# 2_MCU.net
KiCad netlist of a schematic drawn in Altium Designer
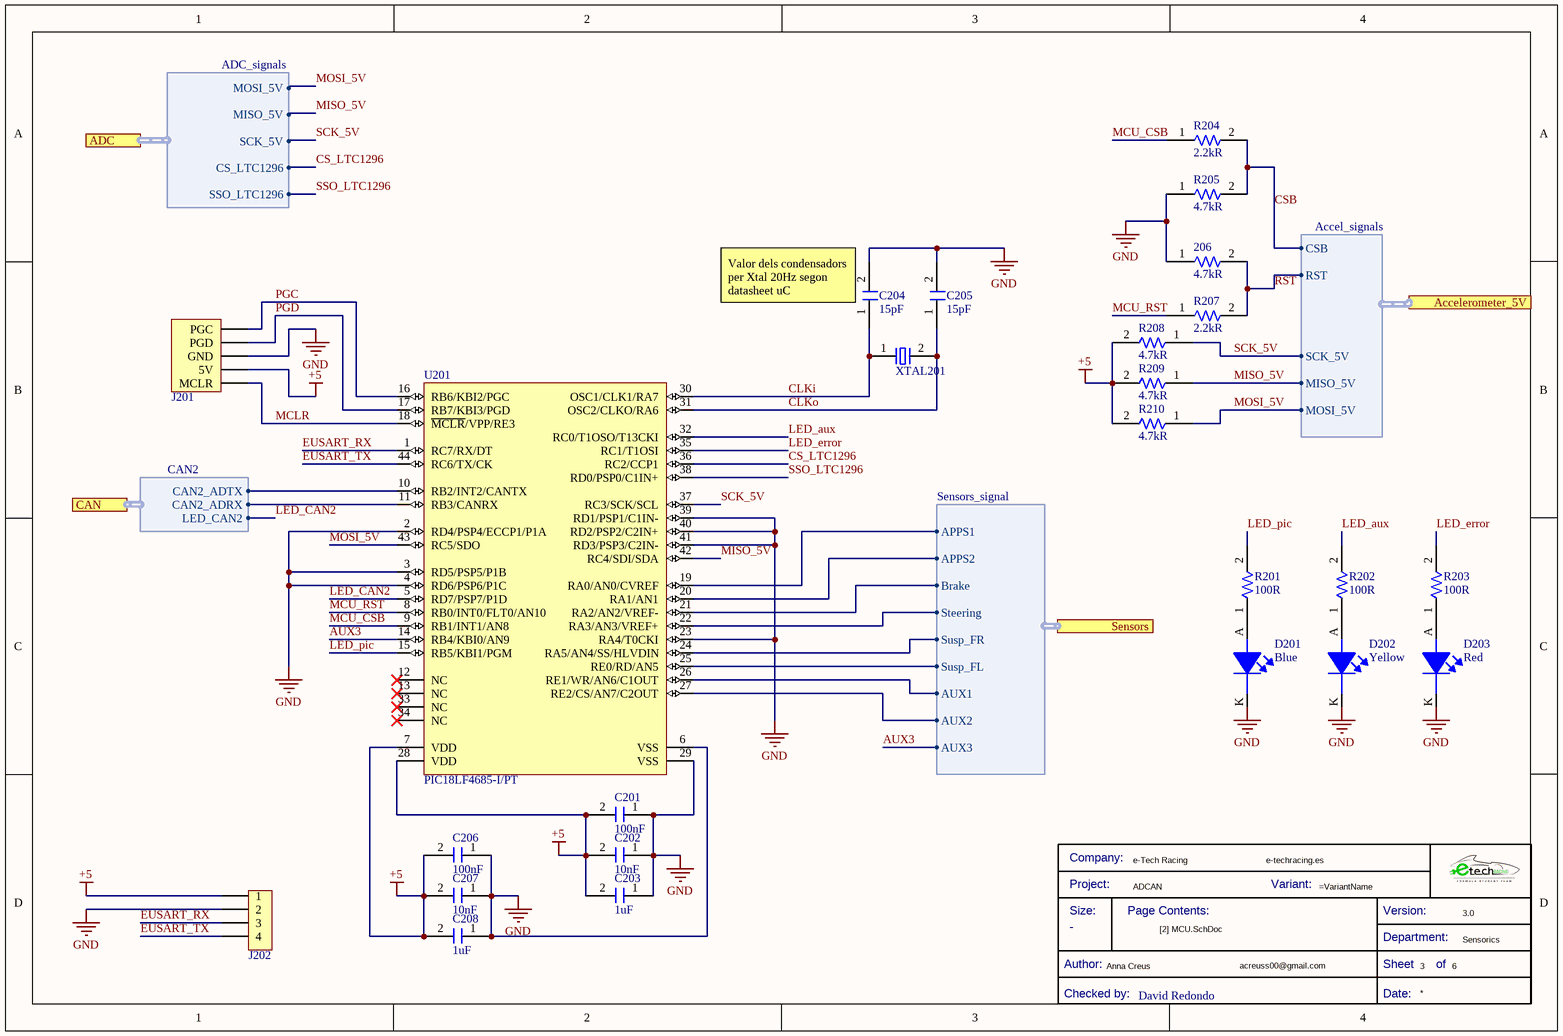
[diagram p0: [2] MCU.SchDoc]

(export (version "E")
  (design (tool "Eeschema 10.0.6"))
  (components
    (comp (ref "206")
      (value "CRS1206-FX-4701ELF")
      (footprint "R1206FTK-W")
      (description "Res Thick Film 1206 4.7K Ohm 1% 1/2W ±100ppm/°C Molded SMD T/R")
      (fields (field (name "TOLERANCE") "1%") (field (name "RESISTANCE") "4.7kR"))
      (libsource (lib "Passives") (part "R4.7K-1206FTK"))
    )
    (comp (ref "C201")
      (value "885012208009")
      (footprint "C1206FNPC-RW")
      (description "Cap, 0.1ΜF, 10V, 10%, X7R, 1206")
      (fields (field (name "TOLERANCE") "10%") (field (name "CAPACITANCE") "100nF"))
      (libsource (lib "Passives") (part "C100n-10V-1206FNPC-X7R"))
    )
    (comp (ref "C202")
      (value "885012208009")
      (footprint "C1206FNPC-RW")
      (description "Cap, 0.1ΜF, 10V, 10%, X7R, 1206")
      (fields (field (name "TOLERANCE") "10%") (field (name "CAPACITANCE") "10nF"))
      (libsource (lib "Passives") (part "C100n-10V-1206FNPC-X7R"))
    )
    (comp (ref "C203")
      (value "885012208009")
      (footprint "C1206FNPC-RW")
      (description "Cap, 0.1ΜF, 10V, 10%, X7R, 1206")
      (fields (field (name "TOLERANCE") "10%") (field (name "CAPACITANCE") "1uF"))
      (libsource (lib "Passives") (part "C100n-10V-1206FNPC-X7R"))
    )
    (comp (ref "C204")
      (value "885012008038")
      (footprint "C1206FNPC-RW")
      (description "Cap, 15Pf, 50V, 5%, C0G/np0, 1206 Rohs Compliant: Yes")
      (fields
        (field (name "MANUFACTURER") "Wurth Electronics")
        (field (name "TOLERANCE") "5%")
        (field (name "CAPACITANCE") "15pF")
      )
      (libsource (lib "Passives") (part "C15p-50V-1206FNPC-NP0"))
    )
    (comp (ref "C205")
      (value "885012008038")
      (footprint "C1206FNPC-RW")
      (description "Cap, 15Pf, 50V, 5%, C0G/np0, 1206 Rohs Compliant: Yes")
      (fields
        (field (name "MANUFACTURER") "Wurth Electronics")
        (field (name "TOLERANCE") "5%")
        (field (name "CAPACITANCE") "15pF")
      )
      (libsource (lib "Passives") (part "C15p-50V-1206FNPC-NP0"))
    )
    (comp (ref "C206")
      (value "885012208009")
      (footprint "C1206FNPC-RW")
      (description "Cap, 0.1ΜF, 10V, 10%, X7R, 1206")
      (fields (field (name "TOLERANCE") "10%") (field (name "CAPACITANCE") "100nF"))
      (libsource (lib "Passives") (part "C100n-10V-1206FNPC-X7R"))
    )
    (comp (ref "C207")
      (value "885012208009")
      (footprint "C1206FNPC-RW")
      (description "Cap, 0.1ΜF, 10V, 10%, X7R, 1206")
      (fields (field (name "TOLERANCE") "10%") (field (name "CAPACITANCE") "10nF"))
      (libsource (lib "Passives") (part "C100n-10V-1206FNPC-X7R"))
    )
    (comp (ref "C208")
      (value "885012208009")
      (footprint "C1206FNPC-RW")
      (description "Cap, 0.1ΜF, 10V, 10%, X7R, 1206")
      (fields (field (name "TOLERANCE") "10%") (field (name "CAPACITANCE") "1uF"))
      (libsource (lib "Passives") (part "C100n-10V-1206FNPC-X7R"))
    )
    (comp (ref "D201")
      (value "150120BS75000")
      (footprint "LED_1206_WE")
      (description "Led, Blue, 470 Nm, 3.2 V, 30 Ma, 145 Mcd Rohs Compliant: Yes")
      (fields (field (name "MANUFACTURER") "Wurth Electronics") (field (name "COLOR") "Blue"))
      (libsource (lib "Semiconductor") (part "LEDBS-1206-145"))
    )
    (comp (ref "D202")
      (value "150120YS75000")
      (footprint "LED_1206_WE")
      (description "Led, Yellow, 590 Nm, 2 V, 30 Ma, 120 Mcd Rohs Compliant: Yes")
      (fields (field (name "MANUFACTURER") "Wurth Electronics") (field (name "COLOR") "Yellow"))
      (libsource (lib "Semiconductor") (part "LEDYS-1206-120"))
    )
    (comp (ref "D203")
      (value "150120RS75000")
      (footprint "LED_1206_WE")
      (description "Led, Red, 625 Nm, 2 V, 30 Ma, 150 Mcd Rohs Compliant: Yes")
      (fields (field (name "MANUFACTURER") "Wurth Electronics") (field (name "COLOR") "Red"))
      (libsource (lib "Semiconductor") (part "LEDRS-1206-150"))
    )
    (comp (ref "J201")
      (value "61300511121")
      (footprint "J_Pinheader_1x5")
      (description "THT Vertical Pin Header WR-PHD, Pitch 2.54 mm, Single Row, 5 pins")
      (fields (field (name "MANUFACTURER") "Molex"))
      (libsource (lib "Electromechanical") (part "J_Bootloader_PIC_5V"))
    )
    (comp (ref "J202")
      (value "61300411121")
      (footprint "J_PinHeader_1x4")
      (description "CONN HEADER 4 POS 2.54")
      (fields (field (name ".CREATOR") "AC"))
      (libsource (lib "Electromechanical") (part "J_UART"))
    )
    (comp (ref "R201")
      (value "CRG1206F100R")
      (footprint "R1206FTK-W")
      (description "Res Thick Film 1206 100 Ohm 1% 0.25W(1/4W) ±200ppm/C Pad SMD T/R")
      (fields
        (field (name "MANUFACTURER") "TE Connectivity")
        (field (name "TOLERANCE") "1%")
        (field (name "RESISTANCE") "100R")
      )
      (libsource (lib "Passives") (part "R100-1206FTK"))
    )
    (comp (ref "R202")
      (value "CRG1206F100R")
      (footprint "R1206FTK-W")
      (description "Res Thick Film 1206 100 Ohm 1% 0.25W(1/4W) ±200ppm/C Pad SMD T/R")
      (fields
        (field (name "MANUFACTURER") "TE Connectivity")
        (field (name "TOLERANCE") "1%")
        (field (name "RESISTANCE") "100R")
      )
      (libsource (lib "Passives") (part "R100-1206FTK"))
    )
    (comp (ref "R203")
      (value "CRG1206F100R")
      (footprint "R1206FTK-W")
      (description "Res Thick Film 1206 100 Ohm 1% 0.25W(1/4W) ±200ppm/C Pad SMD T/R")
      (fields
        (field (name "MANUFACTURER") "TE Connectivity")
        (field (name "TOLERANCE") "1%")
        (field (name "RESISTANCE") "100R")
      )
      (libsource (lib "Passives") (part "R100-1206FTK"))
    )
    (comp (ref "R204")
      (value "CR1206-FX-2201ELF")
      (footprint "R1206FTK-W")
      (description "Res Thick Film 1206 2.2K Ohm 1% 1/4W ±100ppm/°C Molded SMD SMD Paper Tape on Plastic Reel")
      (fields (field (name "TOLERANCE") "1%") (field (name "RESISTANCE") "2.2kR"))
      (libsource (lib "Passives") (part "R2.2K-1206FTK"))
    )
    (comp (ref "R205")
      (value "CRS1206-FX-4701ELF")
      (footprint "R1206FTK-W")
      (description "Res Thick Film 1206 4.7K Ohm 1% 1/2W ±100ppm/°C Molded SMD T/R")
      (fields (field (name "TOLERANCE") "1%") (field (name "RESISTANCE") "4.7kR"))
      (libsource (lib "Passives") (part "R4.7K-1206FTK"))
    )
    (comp (ref "R207")
      (value "CR1206-FX-2201ELF")
      (footprint "R1206FTK-W")
      (description "Res Thick Film 1206 2.2K Ohm 1% 1/4W ±100ppm/°C Molded SMD SMD Paper Tape on Plastic Reel")
      (fields (field (name "TOLERANCE") "1%") (field (name "RESISTANCE") "2.2kR"))
      (libsource (lib "Passives") (part "R2.2K-1206FTK"))
    )
    (comp (ref "R208")
      (value "CRS1206-FX-4701ELF")
      (footprint "R1206FTK-W")
      (description "Res Thick Film 1206 4.7K Ohm 1% 1/2W ±100ppm/°C Molded SMD T/R")
      (fields (field (name "TOLERANCE") "1%") (field (name "RESISTANCE") "4.7kR"))
      (libsource (lib "Passives") (part "R4.7K-1206FTK"))
    )
    (comp (ref "R209")
      (value "CRS1206-FX-4701ELF")
      (footprint "R1206FTK-W")
      (description "Res Thick Film 1206 4.7K Ohm 1% 1/2W ±100ppm/°C Molded SMD T/R")
      (fields (field (name "TOLERANCE") "1%") (field (name "RESISTANCE") "4.7kR"))
      (libsource (lib "Passives") (part "R4.7K-1206FTK"))
    )
    (comp (ref "R210")
      (value "CRS1206-FX-4701ELF")
      (footprint "R1206FTK-W")
      (description "Res Thick Film 1206 4.7K Ohm 1% 1/2W ±100ppm/°C Molded SMD T/R")
      (fields (field (name "TOLERANCE") "1%") (field (name "RESISTANCE") "4.7kR"))
      (libsource (lib "Passives") (part "R4.7K-1206FTK"))
    )
    (comp (ref "U201")
      (value "PIC18LF4685-I/PT")
      (footprint "U_PIC18LF4685-I/PT")
      (description "PIC18 Series 96 kB Flash 3328 B RAM 40 MHz 8-Bit Microcontroller - TQFP-44")
      (fields (field (name "MANUFACTURER") "Microchip") (field (name ".CREATOR") "GP"))
      (libsource (lib "Integrated circuits") (part "U_PIC18LF4685-I/PT_1"))
    )
    (comp (ref "XTAL201")
      (value "830028710")
      (footprint "XTAL20M_SMD")
      (description "830028710, 20 MHz")
      (fields (field (name "MANUFACTURER") "Würth Elektronik"))
      (libsource (lib "Passives") (part "XTAL20M_SMD"))
    )
  )
  (nets
    (net (code "5") (name "+5") (class "Default")
      (node (ref "C201") (pin "2") (pinfunction "2_2") (pintype "passive"))
      (node (ref "C202") (pin "2") (pinfunction "2_2") (pintype "passive"))
      (node (ref "C203") (pin "2") (pinfunction "2_2") (pintype "passive"))
      (node (ref "C206") (pin "2") (pinfunction "2_2") (pintype "passive"))
      (node (ref "C207") (pin "2") (pinfunction "2_2") (pintype "passive"))
      (node (ref "C208") (pin "2") (pinfunction "2_2") (pintype "passive"))
      (node (ref "J201") (pin "2") (pinfunction "5V_2") (pintype "passive"))
      (node (ref "J202") (pin "1") (pinfunction "1_1") (pintype "passive"))
      (node (ref "R208") (pin "2") (pinfunction "2_2") (pintype "passive"))
      (node (ref "R209") (pin "2") (pinfunction "2_2") (pintype "passive"))
      (node (ref "R210") (pin "2") (pinfunction "2_2") (pintype "passive"))
      (node (ref "U201") (pin "28") (pinfunction "VDD_28") (pintype "passive"))
      (node (ref "U201") (pin "7") (pinfunction "VDD_7") (pintype "passive"))
    )
    (net (code "6") (name "/APPS1") (class "Default")
      (node (ref "U201") (pin "19") (pinfunction "RA0/AN0/CVREF_19") (pintype "bidirectional"))
    )
    (net (code "7") (name "/APPS2") (class "Default")
      (node (ref "U201") (pin "20") (pinfunction "RA1/AN1_20") (pintype "bidirectional"))
    )
    (net (code "8") (name "/AUX1") (class "Default")
      (node (ref "U201") (pin "26") (pinfunction "RE1/WR/AN6/C1OUT_26") (pintype "bidirectional"))
    )
    (net (code "9") (name "/AUX2") (class "Default")
      (node (ref "U201") (pin "27") (pinfunction "RE2/CS/AN7/C2OUT_27") (pintype "bidirectional"))
    )
    (net (code "10") (name "/AUX3") (class "Default")
      (node (ref "U201") (pin "14") (pinfunction "RB4/KBI0/AN9_14") (pintype "bidirectional"))
    )
    (net (code "11") (name "/Brake") (class "Default")
      (node (ref "U201") (pin "21") (pinfunction "RA2/AN2/VREF-_21") (pintype "bidirectional"))
    )
    (net (code "12") (name "/CAN2_ADRX") (class "Default")
      (node (ref "U201") (pin "11") (pinfunction "RB3/CANRX_11") (pintype "bidirectional"))
    )
    (net (code "13") (name "/CAN2_ADTX") (class "Default")
      (node (ref "U201") (pin "10") (pinfunction "RB2/INT2/CANTX_10") (pintype "bidirectional"))
    )
    (net (code "14") (name "/CLKi") (class "Default")
      (node (ref "C204") (pin "1") (pinfunction "1_1") (pintype "passive"))
      (node (ref "U201") (pin "30") (pinfunction "OSC1/CLK1/RA7_30") (pintype "bidirectional"))
      (node (ref "XTAL201") (pin "1") (pinfunction "1_1") (pintype "passive"))
    )
    (net (code "15") (name "/CLKo") (class "Default")
      (node (ref "C205") (pin "1") (pinfunction "1_1") (pintype "passive"))
      (node (ref "U201") (pin "31") (pinfunction "OSC2/CLKO/RA6_31") (pintype "bidirectional"))
      (node (ref "XTAL201") (pin "2") (pinfunction "2_2") (pintype "passive"))
    )
    (net (code "16") (name "/CSB") (class "Default")
      (node (ref "R204") (pin "2") (pinfunction "2_2") (pintype "passive"))
      (node (ref "R205") (pin "2") (pinfunction "2_2") (pintype "passive"))
    )
    (net (code "17") (name "/CS_LTC1296") (class "Default")
      (node (ref "U201") (pin "36") (pinfunction "RC2/CCP1_36") (pintype "bidirectional"))
    )
    (net (code "18") (name "/EUSART_RX") (class "Default")
      (node (ref "J202") (pin "3") (pinfunction "3_3") (pintype "passive"))
      (node (ref "U201") (pin "1") (pinfunction "RC7/RX/DT_1") (pintype "bidirectional"))
    )
    (net (code "19") (name "/EUSART_TX") (class "Default")
      (node (ref "J202") (pin "4") (pinfunction "4_4") (pintype "passive"))
      (node (ref "U201") (pin "44") (pinfunction "RC6/TX/CK_44") (pintype "bidirectional"))
    )
    (net (code "20") (name "/LED_CAN2") (class "Default")
      (node (ref "U201") (pin "5") (pinfunction "RD7/PSP7/P1D_5") (pintype "bidirectional"))
    )
    (net (code "21") (name "/LED_aux") (class "Default")
      (node (ref "R202") (pin "2") (pinfunction "2_2") (pintype "passive"))
      (node (ref "U201") (pin "32") (pinfunction "RC0/T1OSO/T13CKI_32") (pintype "bidirectional"))
    )
    (net (code "22") (name "/LED_error") (class "Default")
      (node (ref "R203") (pin "2") (pinfunction "2_2") (pintype "passive"))
      (node (ref "U201") (pin "35") (pinfunction "RC1/T1OSI_35") (pintype "bidirectional"))
    )
    (net (code "23") (name "/LED_pic") (class "Default")
      (node (ref "R201") (pin "2") (pinfunction "2_2") (pintype "passive"))
      (node (ref "U201") (pin "15") (pinfunction "RB5/KBI1/PGM_15") (pintype "bidirectional"))
    )
    (net (code "24") (name "/MCLR") (class "Default")
      (node (ref "J201") (pin "1") (pinfunction "MCLR_1") (pintype "passive"))
      (node (ref "U201") (pin "18") (pinfunction "~{MCLR}/VPP/RE3_18") (pintype "bidirectional"))
    )
    (net (code "25") (name "/MCU_CSB") (class "Default")
      (node (ref "R204") (pin "1") (pinfunction "1_1") (pintype "passive"))
      (node (ref "U201") (pin "9") (pinfunction "RB1/INT1/AN8_9") (pintype "bidirectional"))
    )
    (net (code "26") (name "/MCU_RST") (class "Default")
      (node (ref "R207") (pin "1") (pinfunction "1_1") (pintype "passive"))
      (node (ref "U201") (pin "8") (pinfunction "RB0/INT0/FLT0/AN10_8") (pintype "bidirectional"))
    )
    (net (code "27") (name "/MISO_5V") (class "Default")
      (node (ref "R209") (pin "1") (pinfunction "1_1") (pintype "passive"))
      (node (ref "U201") (pin "42") (pinfunction "RC4/SDI/SDA_42") (pintype "bidirectional"))
    )
    (net (code "28") (name "/MOSI_5V") (class "Default")
      (node (ref "R210") (pin "1") (pinfunction "1_1") (pintype "passive"))
      (node (ref "U201") (pin "43") (pinfunction "RC5/SDO_43") (pintype "bidirectional"))
    )
    (net (code "29") (name "/PGC") (class "Default")
      (node (ref "J201") (pin "5") (pinfunction "PGC_5") (pintype "passive"))
      (node (ref "U201") (pin "16") (pinfunction "RB6/KBI2/PGC_16") (pintype "bidirectional"))
    )
    (net (code "30") (name "/PGD") (class "Default")
      (node (ref "J201") (pin "4") (pinfunction "PGD_4") (pintype "passive"))
      (node (ref "U201") (pin "17") (pinfunction "RB7/KBI3/PGD_17") (pintype "bidirectional"))
    )
    (net (code "31") (name "/RST") (class "Default")
      (node (ref "206") (pin "2") (pinfunction "2_2") (pintype "passive"))
      (node (ref "R207") (pin "2") (pinfunction "2_2") (pintype "passive"))
    )
    (net (code "32") (name "/SCK_5V") (class "Default")
      (node (ref "R208") (pin "1") (pinfunction "1_1") (pintype "passive"))
      (node (ref "U201") (pin "37") (pinfunction "RC3/SCK/SCL_37") (pintype "bidirectional"))
    )
    (net (code "33") (name "/SSO_LTC1296") (class "Default")
      (node (ref "U201") (pin "38") (pinfunction "RD0/PSP0/C1IN+_38") (pintype "bidirectional"))
    )
    (net (code "34") (name "/Steering") (class "Default")
      (node (ref "U201") (pin "22") (pinfunction "RA3/AN3/VREF+_22") (pintype "bidirectional"))
    )
    (net (code "35") (name "/Susp_FL") (class "Default")
      (node (ref "U201") (pin "25") (pinfunction "RE0/RD/AN5_25") (pintype "bidirectional"))
    )
    (net (code "36") (name "/Susp_FR") (class "Default")
      (node (ref "U201") (pin "24") (pinfunction "RA5/AN4/SS/HLVDIN_24") (pintype "bidirectional"))
    )
    (net (code "41") (name "GND") (class "Default")
      (node (ref "206") (pin "1") (pinfunction "1_1") (pintype "passive"))
      (node (ref "C201") (pin "1") (pinfunction "1_1") (pintype "passive"))
      (node (ref "C202") (pin "1") (pinfunction "1_1") (pintype "passive"))
      (node (ref "C203") (pin "1") (pinfunction "1_1") (pintype "passive"))
      (node (ref "C204") (pin "2") (pinfunction "2_2") (pintype "passive"))
      (node (ref "C205") (pin "2") (pinfunction "2_2") (pintype "passive"))
      (node (ref "C206") (pin "1") (pinfunction "1_1") (pintype "passive"))
      (node (ref "C207") (pin "1") (pinfunction "1_1") (pintype "passive"))
      (node (ref "C208") (pin "1") (pinfunction "1_1") (pintype "passive"))
      (node (ref "D201") (pin "K") (pinfunction "K_K") (pintype "passive"))
      (node (ref "D202") (pin "K") (pinfunction "K_K") (pintype "passive"))
      (node (ref "D203") (pin "K") (pinfunction "K_K") (pintype "passive"))
      (node (ref "J201") (pin "3") (pinfunction "GND_3") (pintype "passive"))
      (node (ref "J202") (pin "2") (pinfunction "2_2") (pintype "passive"))
      (node (ref "R205") (pin "1") (pinfunction "1_1") (pintype "passive"))
      (node (ref "U201") (pin "2") (pinfunction "RD4/PSP4/ECCP1/P1A_2") (pintype "bidirectional"))
      (node (ref "U201") (pin "23") (pinfunction "RA4/T0CKI_23") (pintype "bidirectional"))
      (node (ref "U201") (pin "29") (pinfunction "VSS_29") (pintype "passive"))
      (node (ref "U201") (pin "3") (pinfunction "RD5/PSP5/P1B_3") (pintype "bidirectional"))
      (node (ref "U201") (pin "39") (pinfunction "RD1/PSP1/C1IN-_39") (pintype "bidirectional"))
      (node (ref "U201") (pin "4") (pinfunction "RD6/PSP6/P1C_4") (pintype "bidirectional"))
      (node (ref "U201") (pin "40") (pinfunction "RD2/PSP2/C2IN+_40") (pintype "bidirectional"))
      (node (ref "U201") (pin "41") (pinfunction "RD3/PSP3/C2IN-_41") (pintype "bidirectional"))
      (node (ref "U201") (pin "6") (pinfunction "VSS_6") (pintype "passive"))
    )
    (net (code "42") (name "Net-(D201-PadA)") (class "Default")
      (node (ref "D201") (pin "A") (pinfunction "A_A") (pintype "passive"))
      (node (ref "R201") (pin "1") (pinfunction "1_1") (pintype "passive"))
    )
    (net (code "43") (name "Net-(D202-PadA)") (class "Default")
      (node (ref "D202") (pin "A") (pinfunction "A_A") (pintype "passive"))
      (node (ref "R202") (pin "1") (pinfunction "1_1") (pintype "passive"))
    )
    (net (code "44") (name "Net-(D203-PadA)") (class "Default")
      (node (ref "D203") (pin "A") (pinfunction "A_A") (pintype "passive"))
      (node (ref "R203") (pin "1") (pinfunction "1_1") (pintype "passive"))
    )
    (net (code "45") (name "unconnected-(U201-NC-Pad12)") (class "Default")
      (node (ref "U201") (pin "12") (pinfunction "NC_12") (pintype "passive+no_connect"))
    )
    (net (code "46") (name "unconnected-(U201-NC-Pad13)") (class "Default")
      (node (ref "U201") (pin "13") (pinfunction "NC_13") (pintype "passive+no_connect"))
    )
    (net (code "47") (name "unconnected-(U201-NC-Pad33)") (class "Default")
      (node (ref "U201") (pin "33") (pinfunction "NC_33") (pintype "passive+no_connect"))
    )
    (net (code "48") (name "unconnected-(U201-NC-Pad34)") (class "Default")
      (node (ref "U201") (pin "34") (pinfunction "NC_34") (pintype "passive+no_connect"))
    )
  )
)
